# 4_relay_5Switch.net
KiCad netlist of a schematic drawn in EAGLE
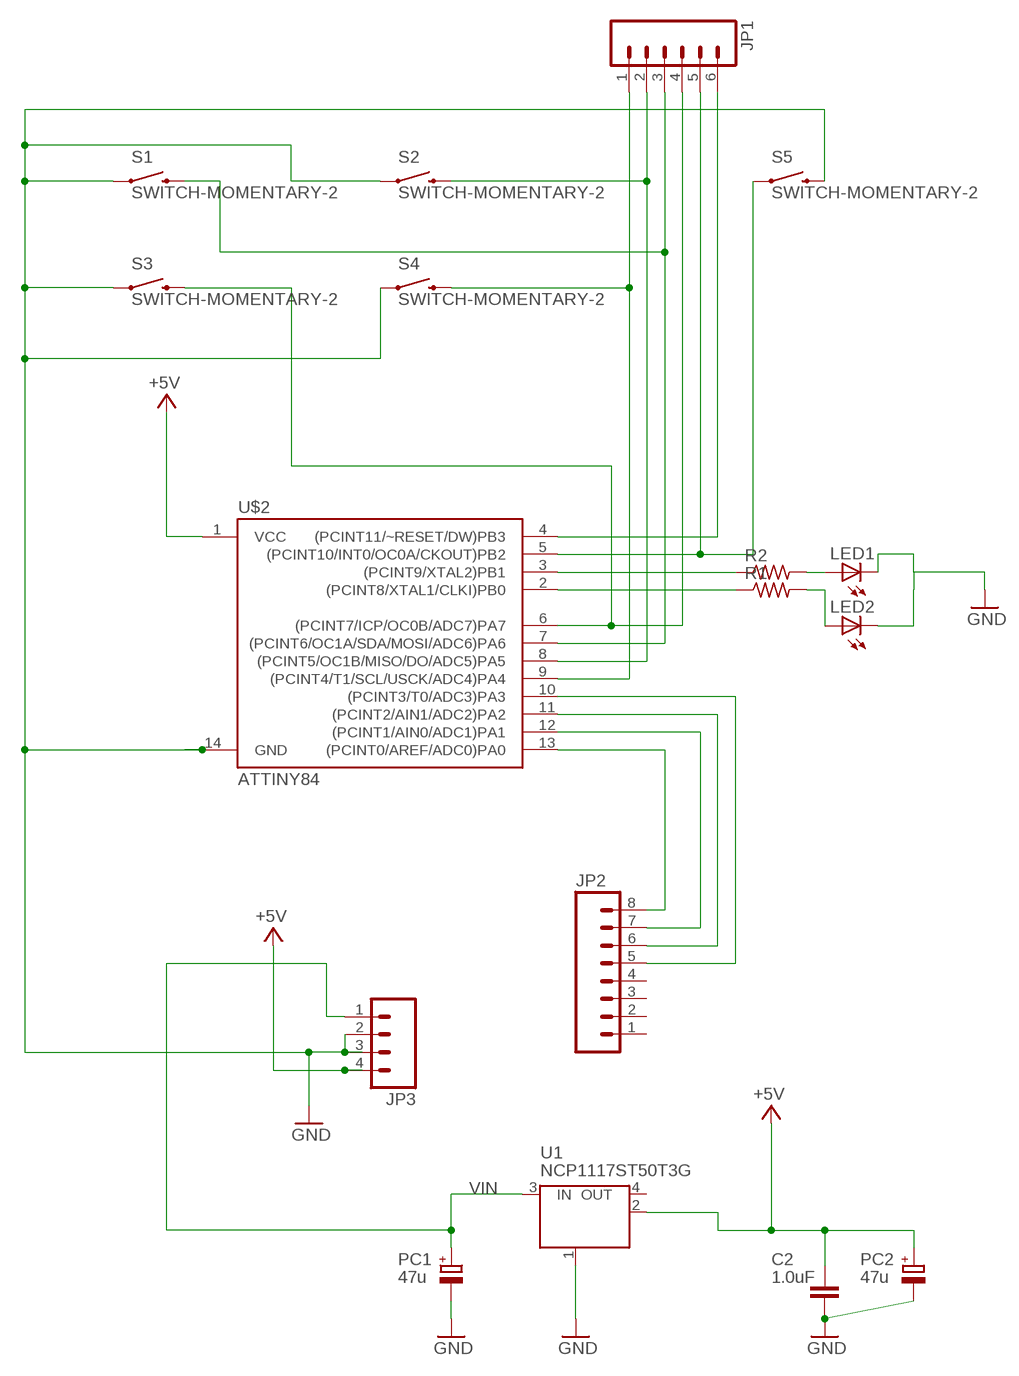
[diagram p0: schematic, sheet 1]

(export (version "E")
  (design (tool "Eeschema 10.0.6"))
  (components
    (comp (ref "C2")
      (value "1.0uF")
      (footprint "eagle-import:0805")
      (libsource (lib "eagle-import") (part "1.0UF-25V-+80/-20(0805)"))
    )
    (comp (ref "JP1")
      (value "M06NO_SILK_FEMALE_PTH")
      (footprint "eagle-import:1X06_NO_SILK")
      (libsource (lib "eagle-import") (part "M06NO_SILK_FEMALE_PTH"))
    )
    (comp (ref "JP2")
      (value "M08NO_SILK")
      (footprint "eagle-import:1X08_PIN1_NO_SILK")
      (libsource (lib "eagle-import") (part "M08NO_SILK"))
    )
    (comp (ref "JP3")
      (value "M041X04_NO_SILK")
      (footprint "eagle-import:1X04_NO_SILK")
      (libsource (lib "eagle-import") (part "M041X04_NO_SILK"))
    )
    (comp (ref "LED1")
      (value "LEDCHIP-LED0805")
      (footprint "eagle-import:CHIP-LED0805")
      (libsource (lib "eagle-import") (part "LEDCHIP-LED0805"))
    )
    (comp (ref "LED2")
      (value "LEDCHIP-LED0805")
      (footprint "eagle-import:CHIP-LED0805")
      (libsource (lib "eagle-import") (part "LEDCHIP-LED0805"))
    )
    (comp (ref "PC1")
      (value "47u")
      (footprint "eagle-import:E2,5-4R")
      (libsource (lib "eagle-import") (part "CPOL-EUE2.5-5V"))
    )
    (comp (ref "PC2")
      (value "47u")
      (footprint "eagle-import:E2,5-4R")
      (libsource (lib "eagle-import") (part "CPOL-EUE2.5-5V"))
    )
    (comp (ref "R1")
      (value "R-US_R0805")
      (footprint "eagle-import:R0805")
      (libsource (lib "eagle-import") (part "R-US_R0805"))
    )
    (comp (ref "R2")
      (value "R-US_R0805")
      (footprint "eagle-import:R0805")
      (libsource (lib "eagle-import") (part "R-US_R0805"))
    )
    (comp (ref "S1")
      (value "SWITCH-MOMENTARY-2")
      (footprint "eagle-import:TACTILE_FSM4JSMATR")
      (libsource (lib "eagle-import") (part "SWITCH-MOMENTARY-2"))
    )
    (comp (ref "S2")
      (value "SWITCH-MOMENTARY-2")
      (footprint "eagle-import:TACTILE_FSM4JSMATR")
      (libsource (lib "eagle-import") (part "SWITCH-MOMENTARY-2"))
    )
    (comp (ref "S3")
      (value "SWITCH-MOMENTARY-2")
      (footprint "eagle-import:TACTILE_FSM4JSMATR")
      (libsource (lib "eagle-import") (part "SWITCH-MOMENTARY-2"))
    )
    (comp (ref "S4")
      (value "SWITCH-MOMENTARY-2")
      (footprint "eagle-import:TACTILE_FSM4JSMATR")
      (libsource (lib "eagle-import") (part "SWITCH-MOMENTARY-2"))
    )
    (comp (ref "S5")
      (value "SWITCH-MOMENTARY-2")
      (footprint "eagle-import:TACTILE_FSM4JSMATR")
      (libsource (lib "eagle-import") (part "SWITCH-MOMENTARY-2"))
    )
    (comp (ref "U$2")
      (value "ATTINY84")
      (footprint "eagle-import:SO14")
      (libsource (lib "eagle-import") (part "ATTINY84"))
    )
    (comp (ref "U1")
      (value "NCP1117ST50T3G")
      (footprint "eagle-import:SOT223")
      (libsource (lib "eagle-import") (part "MC33269ST-3.3T3"))
    )
  )
  (nets
    (net (code "1") (name "+5V") (class "Default")
      (node (ref "C2") (pin "2") (pinfunction "2_2") (pintype "passive"))
      (node (ref "JP3") (pin "4") (pinfunction "4_4") (pintype "passive"))
      (node (ref "PC2") (pin "+") (pinfunction "+_+") (pintype "passive"))
      (node (ref "U$2") (pin "1") (pinfunction "VCC_1") (pintype "bidirectional"))
      (node (ref "U1") (pin "2") (pinfunction "OUT_2") (pintype "passive"))
    )
    (net (code "2") (name "/VIN") (class "Default")
      (node (ref "JP3") (pin "1") (pinfunction "1_1") (pintype "passive"))
      (node (ref "PC1") (pin "+") (pinfunction "+_+") (pintype "passive"))
      (node (ref "U1") (pin "3") (pinfunction "IN_3") (pintype "input"))
    )
    (net (code "3") (name "GND") (class "Default")
      (node (ref "C2") (pin "1") (pinfunction "1_1") (pintype "passive"))
      (node (ref "JP3") (pin "2") (pinfunction "2_2") (pintype "passive"))
      (node (ref "JP3") (pin "3") (pinfunction "3_3") (pintype "passive"))
      (node (ref "LED1") (pin "C") (pinfunction "C_C") (pintype "passive"))
      (node (ref "LED2") (pin "C") (pinfunction "C_C") (pintype "passive"))
      (node (ref "PC1") (pin "-") (pinfunction "-_-") (pintype "passive"))
      (node (ref "PC2") (pin "-") (pinfunction "-_-") (pintype "passive"))
      (node (ref "S1") (pin "P$1") (pinfunction "1_P$1") (pintype "passive"))
      (node (ref "S1") (pin "P$2") (pinfunction "1_P$2") (pintype "passive"))
      (node (ref "S2") (pin "P$1") (pinfunction "1_P$1") (pintype "passive"))
      (node (ref "S2") (pin "P$2") (pinfunction "1_P$2") (pintype "passive"))
      (node (ref "S3") (pin "P$1") (pinfunction "1_P$1") (pintype "passive"))
      (node (ref "S3") (pin "P$2") (pinfunction "1_P$2") (pintype "passive"))
      (node (ref "S4") (pin "P$1") (pinfunction "1_P$1") (pintype "passive"))
      (node (ref "S4") (pin "P$2") (pinfunction "1_P$2") (pintype "passive"))
      (node (ref "S5") (pin "P$3") (pinfunction "2_P$3") (pintype "passive"))
      (node (ref "S5") (pin "P$4") (pinfunction "2_P$4") (pintype "passive"))
      (node (ref "U$2") (pin "14") (pinfunction "GND_14") (pintype "bidirectional"))
      (node (ref "U1") (pin "1") (pinfunction "GND/ADJ_1") (pintype "input"))
    )
    (net (code "4") (name "Net-(LED1-PadA)") (class "Default")
      (node (ref "LED1") (pin "A") (pinfunction "A_A") (pintype "passive"))
      (node (ref "R2") (pin "2") (pinfunction "2_2") (pintype "passive"))
    )
    (net (code "5") (name "Net-(LED2-PadA)") (class "Default")
      (node (ref "LED2") (pin "A") (pinfunction "A_A") (pintype "passive"))
      (node (ref "R1") (pin "2") (pinfunction "2_2") (pintype "passive"))
    )
    (net (code "6") (name "Net-(U$2-(PCINT0{slash}AREF{slash}ADC0)PA0)") (class "Default")
      (node (ref "JP2") (pin "8") (pinfunction "8_8") (pintype "passive"))
      (node (ref "U$2") (pin "13") (pinfunction "(PCINT0/AREF/ADC0)PA0_13") (pintype "bidirectional"))
    )
    (net (code "7") (name "Net-(U$2-(PCINT1{slash}AIN0{slash}ADC1)PA1)") (class "Default")
      (node (ref "JP2") (pin "7") (pinfunction "7_7") (pintype "passive"))
      (node (ref "U$2") (pin "12") (pinfunction "(PCINT1/AIN0/ADC1)PA1_12") (pintype "bidirectional"))
    )
    (net (code "8") (name "Net-(U$2-(PCINT2{slash}AIN1{slash}ADC2)PA2)") (class "Default")
      (node (ref "JP2") (pin "6") (pinfunction "6_6") (pintype "passive"))
      (node (ref "U$2") (pin "11") (pinfunction "(PCINT2/AIN1/ADC2)PA2_11") (pintype "bidirectional"))
    )
    (net (code "9") (name "Net-(U$2-(PCINT3{slash}T0{slash}ADC3)PA3)") (class "Default")
      (node (ref "JP2") (pin "5") (pinfunction "5_5") (pintype "passive"))
      (node (ref "U$2") (pin "10") (pinfunction "(PCINT3/T0/ADC3)PA3_10") (pintype "bidirectional"))
    )
    (net (code "10") (name "Net-(U$2-(PCINT4{slash}T1{slash}SCL{slash}USCK{slash}ADC4)PA4)") (class "Default")
      (node (ref "JP1") (pin "1") (pinfunction "1_1") (pintype "passive"))
      (node (ref "S4") (pin "P$3") (pinfunction "2_P$3") (pintype "passive"))
      (node (ref "S4") (pin "P$4") (pinfunction "2_P$4") (pintype "passive"))
      (node (ref "U$2") (pin "9") (pinfunction "(PCINT4/T1/SCL/USCK/ADC4)PA4_9") (pintype "bidirectional"))
    )
    (net (code "11") (name "Net-(U$2-(PCINT5{slash}OC1B{slash}MISO{slash}DO{slash}ADC5)PA5)") (class "Default")
      (node (ref "JP1") (pin "2") (pinfunction "2_2") (pintype "passive"))
      (node (ref "S2") (pin "P$3") (pinfunction "2_P$3") (pintype "passive"))
      (node (ref "S2") (pin "P$4") (pinfunction "2_P$4") (pintype "passive"))
      (node (ref "U$2") (pin "8") (pinfunction "(PCINT5/OC1B/MISO/DO/ADC5)PA5_8") (pintype "bidirectional"))
    )
    (net (code "12") (name "Net-(U$2-(PCINT6{slash}OC1A{slash}SDA{slash}MOSI{slash}ADC6)PA6)") (class "Default")
      (node (ref "JP1") (pin "3") (pinfunction "3_3") (pintype "passive"))
      (node (ref "S1") (pin "P$3") (pinfunction "2_P$3") (pintype "passive"))
      (node (ref "S1") (pin "P$4") (pinfunction "2_P$4") (pintype "passive"))
      (node (ref "U$2") (pin "7") (pinfunction "(PCINT6/OC1A/SDA/MOSI/ADC6)PA6_7") (pintype "bidirectional"))
    )
    (net (code "13") (name "Net-(U$2-(PCINT7{slash}ICP{slash}OC0B{slash}ADC7)PA7)") (class "Default")
      (node (ref "JP1") (pin "4") (pinfunction "4_4") (pintype "passive"))
      (node (ref "S3") (pin "P$3") (pinfunction "2_P$3") (pintype "passive"))
      (node (ref "S3") (pin "P$4") (pinfunction "2_P$4") (pintype "passive"))
      (node (ref "U$2") (pin "6") (pinfunction "(PCINT7/ICP/OC0B/ADC7)PA7_6") (pintype "bidirectional"))
    )
    (net (code "14") (name "Net-(U$2-(PCINT8{slash}XTAL1{slash}CLKI)PB0)") (class "Default")
      (node (ref "R1") (pin "1") (pinfunction "1_1") (pintype "passive"))
      (node (ref "U$2") (pin "2") (pinfunction "(PCINT8/XTAL1/CLKI)PB0_2") (pintype "bidirectional"))
    )
    (net (code "15") (name "Net-(U$2-(PCINT9{slash}XTAL2)PB1)") (class "Default")
      (node (ref "R2") (pin "1") (pinfunction "1_1") (pintype "passive"))
      (node (ref "U$2") (pin "3") (pinfunction "(PCINT9/XTAL2)PB1_3") (pintype "bidirectional"))
    )
    (net (code "16") (name "Net-(U$2-(PCINT10{slash}INT0{slash}OC0A{slash}CKOUT)PB2)") (class "Default")
      (node (ref "JP1") (pin "5") (pinfunction "5_5") (pintype "passive"))
      (node (ref "S5") (pin "P$1") (pinfunction "1_P$1") (pintype "passive"))
      (node (ref "S5") (pin "P$2") (pinfunction "1_P$2") (pintype "passive"))
      (node (ref "U$2") (pin "5") (pinfunction "(PCINT10/INT0/OC0A/CKOUT)PB2_5") (pintype "bidirectional"))
    )
    (net (code "17") (name "Net-(U$2-(PCINT11{slash}~{RESET{slash}DW})PB3)") (class "Default")
      (node (ref "JP1") (pin "6") (pinfunction "6_6") (pintype "passive"))
      (node (ref "U$2") (pin "4") (pinfunction "(PCINT11/~{RESET/DW})PB3_4") (pintype "bidirectional"))
    )
    (net (code "18") (name "unconnected-(JP2-Pad1)") (class "Default")
      (node (ref "JP2") (pin "1") (pinfunction "1_1") (pintype "passive"))
    )
    (net (code "19") (name "unconnected-(JP2-Pad2)") (class "Default")
      (node (ref "JP2") (pin "2") (pinfunction "2_2") (pintype "passive"))
    )
    (net (code "20") (name "unconnected-(JP2-Pad3)") (class "Default")
      (node (ref "JP2") (pin "3") (pinfunction "3_3") (pintype "passive"))
    )
    (net (code "21") (name "unconnected-(JP2-Pad4)") (class "Default")
      (node (ref "JP2") (pin "4") (pinfunction "4_4") (pintype "passive"))
    )
    (net (code "22") (name "unconnected-(U1-OUT-Pad4)") (class "Default")
      (node (ref "U1") (pin "4") (pinfunction "OUT_4") (pintype "passive"))
    )
  )
)
